# MIPI_DSI_TP.net
KiCad netlist of a schematic drawn in Altium Designer
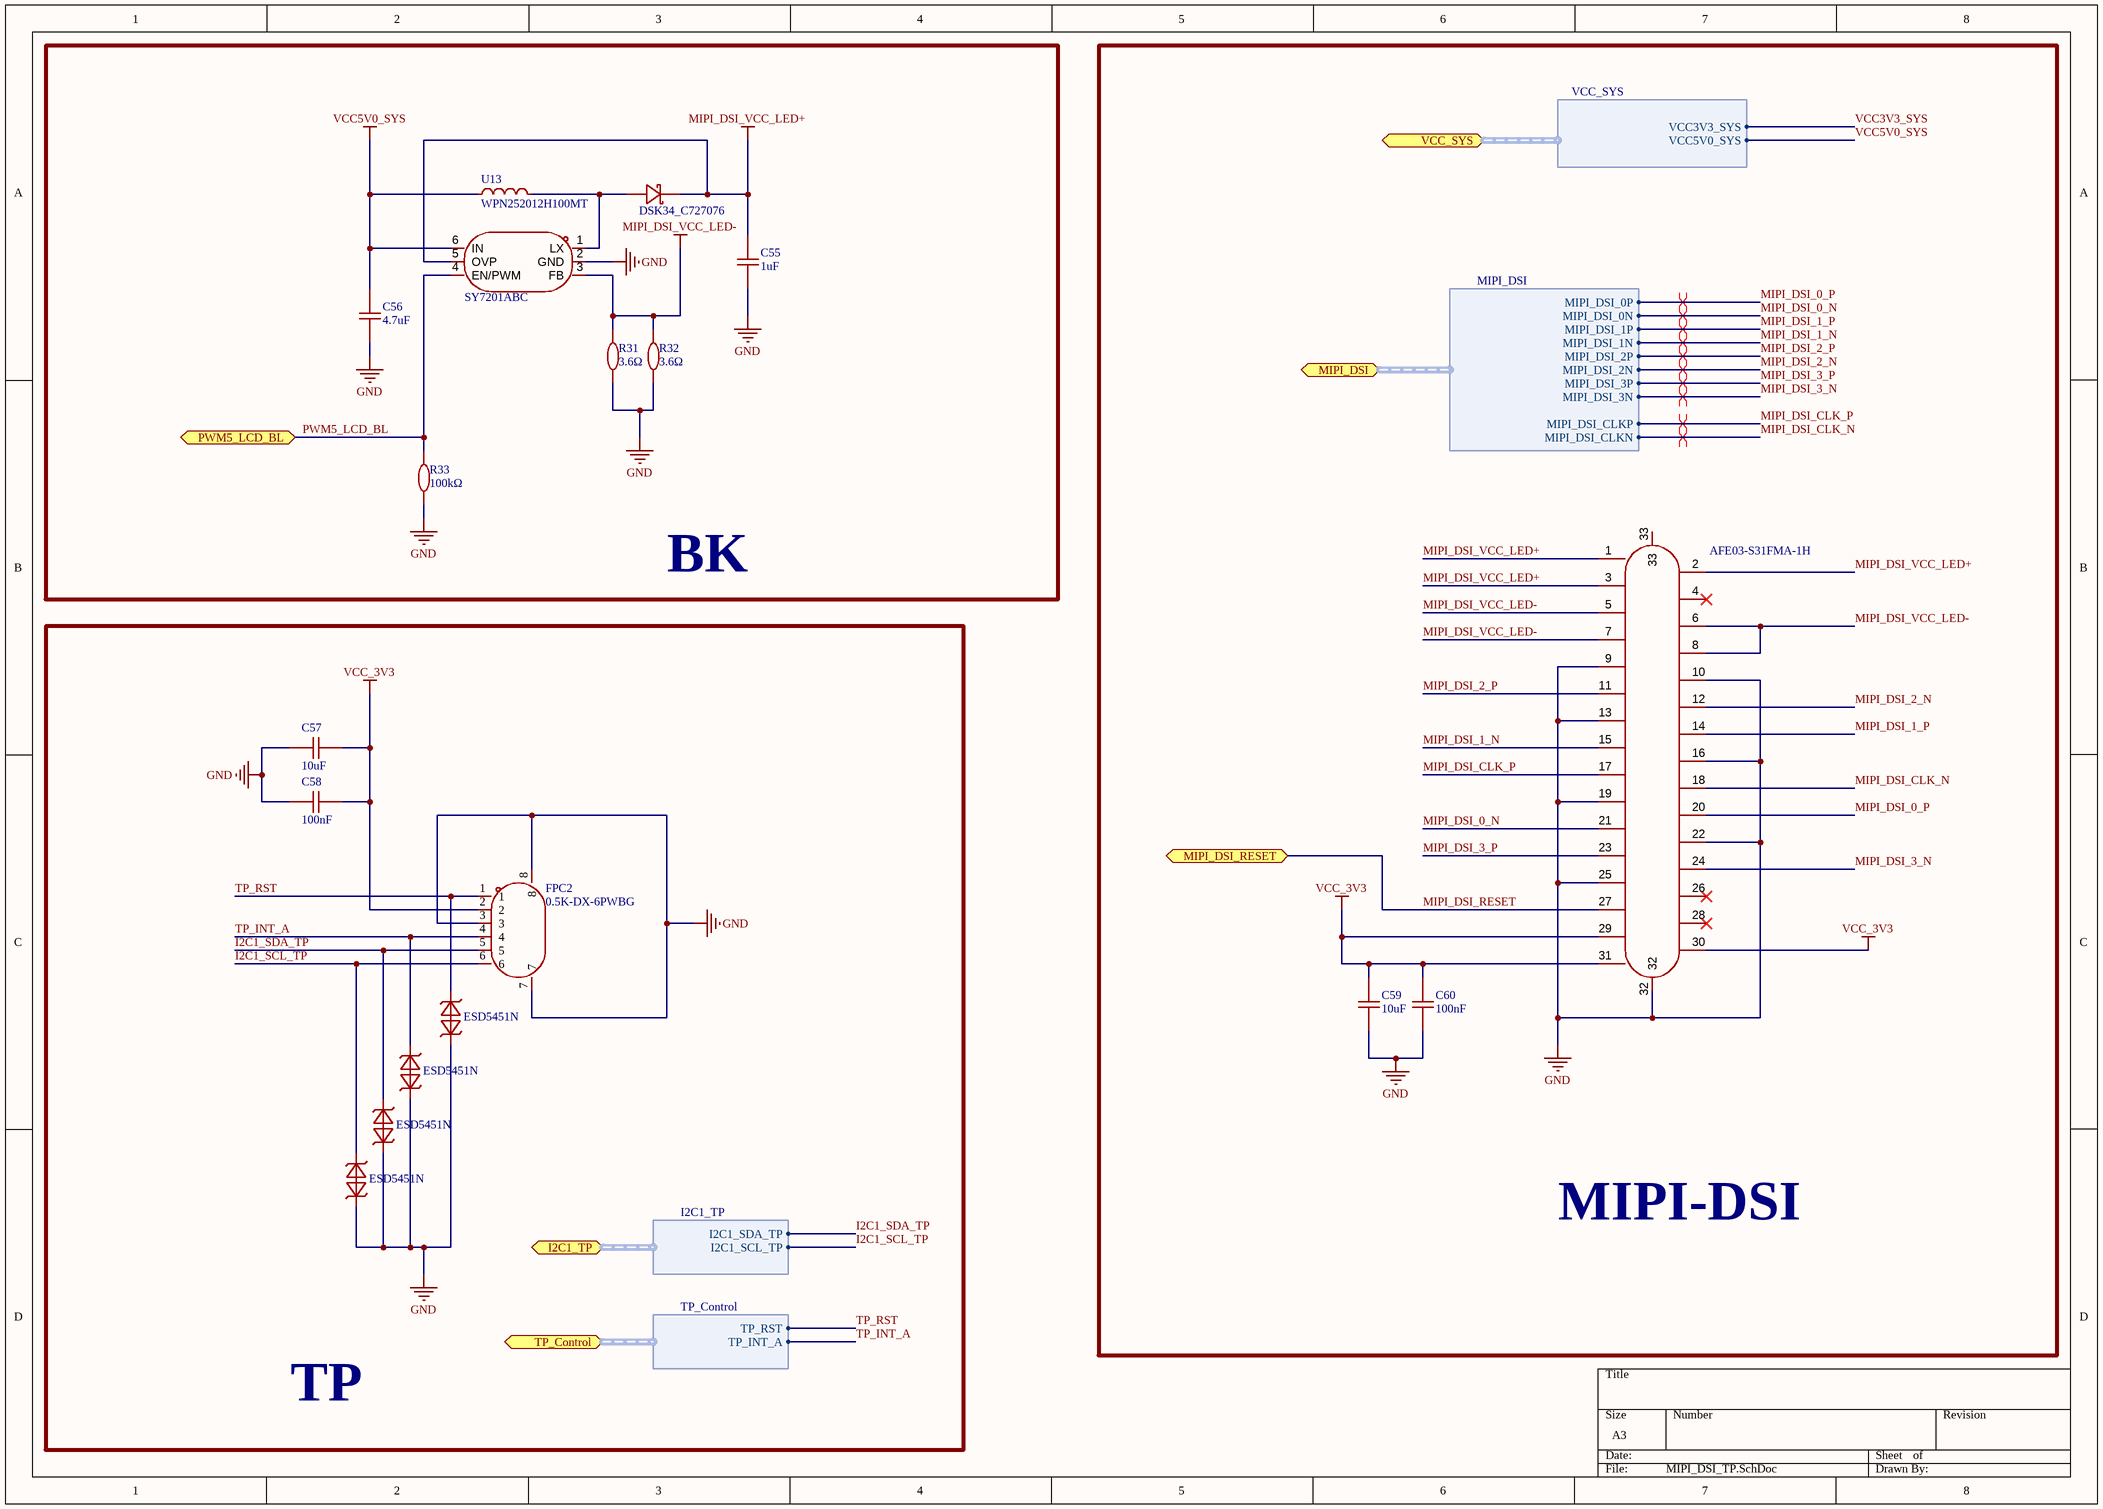
[diagram p0: MIPI_DSI_TP.SchDoc]

(export (version "E")
  (design (tool "Eeschema 10.0.6"))
  (components
    (comp (ref "C55")
      (value "1uF")
      (footprint "C0402")
      (description "50V 1uF X5R ±10% 0402 Ceramic Capacitors ROHS")
      (libsource (lib "RLC") (part "1uF"))
    )
    (comp (ref "C56")
      (value "4.7uF")
      (footprint "C0402")
      (description "10V 4.7uF X5R ±20% 0402 Ceramic Capacitors ROHS")
      (libsource (lib "RLC") (part "4.7uF"))
    )
    (comp (ref "C57")
      (value "10uF")
      (footprint "C0603")
      (description "10V 10uF X5R ±10% 0603 Ceramic Capacitors ROHS")
      (libsource (lib "RLC") (part "10uF"))
    )
    (comp (ref "C58")
      (value "100nF")
      (footprint "C0402")
      (description "50V 100nF X7R ±10% 0402 Ceramic Capacitors ROHS")
      (libsource (lib "RLC") (part "100nF"))
    )
    (comp (ref "C59")
      (value "10uF")
      (footprint "C0603")
      (description "10V 10uF X5R ±10% 0603 Ceramic Capacitors ROHS")
      (libsource (lib "RLC") (part "10uF"))
    )
    (comp (ref "C60")
      (value "100nF")
      (footprint "C0402")
      (description "50V 100nF X7R ±10% 0402 Ceramic Capacitors ROHS")
      (libsource (lib "RLC") (part "100nF"))
    )
    (comp (ref "D8")
      (value "DSK34_C727076")
      (footprint "SOD-323_L1.8-W1.3-LS2.5-RD")
      (libsource (lib "LED") (part "DSK34_C727076"))
    )
    (comp (ref "FPC1")
      (value "AFE03-S31FMA-1H")
      (footprint "FPC-SMD_P0.30-31P_FGS-XJ-H1.0")
      (description "FPC SMD,P=0.3mm,卧贴")
      (libsource (lib "Connector") (part "AFE03-S31FMA-1H"))
    )
    (comp (ref "FPC2")
      (value "0.5K-DX-6PWBG")
      (footprint "FPC-SMD_6P-P0.50_DEALON_0.5K-DX-6PWB")
      (libsource (lib "Connector") (part "0.5K-DX-6PWBG"))
    )
    (comp (ref "R31")
      (value "3.6Ω")
      (footprint "R0603")
      (description "0603 3.6Ω ±1% 100mW 厚膜电阻")
      (libsource (lib "RLC") (part "3.6Ω"))
    )
    (comp (ref "R32")
      (value "3.6Ω")
      (footprint "R0603")
      (description "0603 3.6Ω ±1% 100mW 厚膜电阻")
      (libsource (lib "RLC") (part "3.6Ω"))
    )
    (comp (ref "R33")
      (value "100kΩ")
      (footprint "R0402")
      (description "100kΩ 62.5mW 50V ±100ppm/℃ Thick Film Resistor ±1% 0402 Chip Resistor - Surface Mount ROHS")
      (libsource (lib "RLC") (part "100kΩ"))
    )
    (comp (ref "U13")
      (value "WPN252012H100MT")
      (footprint "IND-SMD_L2.5-W2.0_WPN252012H")
      (description "10uH")
      (libsource (lib "RLC") (part "WPN252012H100MT"))
    )
    (comp (ref "U14")
      (value "SY7201ABC")
      (footprint "SOT-23-6_L2.9-W1.6-P0.95-LS2.8-BR")
      (libsource (lib "IC") (part "SY7201ABC"))
    )
    (comp (ref "U15")
      (value "ESD5451N")
      (footprint "DFN1006-2L-BI")
      (description "是双向 TVS（瞬态电压抑制器），专门用于保护连接到低速数据线和控制线的敏感电子元件，使其免受 ESD（静电放电）、EFT（电快速瞬变）和浪涌引起的过应力影响。")
      (libsource (lib "LED") (part "ESD5451N"))
    )
    (comp (ref "U16")
      (value "ESD5451N")
      (footprint "DFN1006-2L-BI")
      (description "是双向 TVS（瞬态电压抑制器），专门用于保护连接到低速数据线和控制线的敏感电子元件，使其免受 ESD（静电放电）、EFT（电快速瞬变）和浪涌引起的过应力影响。")
      (libsource (lib "LED") (part "ESD5451N"))
    )
    (comp (ref "U17")
      (value "ESD5451N")
      (footprint "DFN1006-2L-BI")
      (description "是双向 TVS（瞬态电压抑制器），专门用于保护连接到低速数据线和控制线的敏感电子元件，使其免受 ESD（静电放电）、EFT（电快速瞬变）和浪涌引起的过应力影响。")
      (libsource (lib "LED") (part "ESD5451N"))
    )
    (comp (ref "U18")
      (value "ESD5451N")
      (footprint "DFN1006-2L-BI")
      (description "是双向 TVS（瞬态电压抑制器），专门用于保护连接到低速数据线和控制线的敏感电子元件，使其免受 ESD（静电放电）、EFT（电快速瞬变）和浪涌引起的过应力影响。")
      (libsource (lib "LED") (part "ESD5451N"))
    )
  )
  (nets
    (net (code "5") (name "/I2C1_SCL_TP") (class "Default")
      (node (ref "FPC2") (pin "6") (pinfunction "6_6") (pintype "passive"))
      (node (ref "U18") (pin "2") (pinfunction "2_2") (pintype "passive"))
    )
    (net (code "6") (name "/I2C1_SDA_TP") (class "Default")
      (node (ref "FPC2") (pin "5") (pinfunction "5_5") (pintype "passive"))
      (node (ref "U17") (pin "2") (pinfunction "2_2") (pintype "passive"))
    )
    (net (code "7") (name "/MIPI_DSI_0_N") (class "Default")
      (node (ref "FPC1") (pin "21") (pinfunction "21_21") (pintype "passive"))
    )
    (net (code "8") (name "/MIPI_DSI_0_P") (class "Default")
      (node (ref "FPC1") (pin "20") (pinfunction "20_20") (pintype "passive"))
    )
    (net (code "9") (name "/MIPI_DSI_1_N") (class "Default")
      (node (ref "FPC1") (pin "15") (pinfunction "15_15") (pintype "passive"))
    )
    (net (code "10") (name "/MIPI_DSI_1_P") (class "Default")
      (node (ref "FPC1") (pin "14") (pinfunction "14_14") (pintype "passive"))
    )
    (net (code "11") (name "/MIPI_DSI_2_N") (class "Default")
      (node (ref "FPC1") (pin "12") (pinfunction "12_12") (pintype "passive"))
    )
    (net (code "12") (name "/MIPI_DSI_2_P") (class "Default")
      (node (ref "FPC1") (pin "11") (pinfunction "11_11") (pintype "passive"))
    )
    (net (code "13") (name "/MIPI_DSI_3_N") (class "Default")
      (node (ref "FPC1") (pin "24") (pinfunction "24_24") (pintype "passive"))
    )
    (net (code "14") (name "/MIPI_DSI_3_P") (class "Default")
      (node (ref "FPC1") (pin "23") (pinfunction "23_23") (pintype "passive"))
    )
    (net (code "15") (name "/MIPI_DSI_CLK_N") (class "Default")
      (node (ref "FPC1") (pin "18") (pinfunction "18_18") (pintype "passive"))
    )
    (net (code "16") (name "/MIPI_DSI_CLK_P") (class "Default")
      (node (ref "FPC1") (pin "17") (pinfunction "17_17") (pintype "passive"))
    )
    (net (code "17") (name "/MIPI_DSI_RESET") (class "Default")
      (node (ref "FPC1") (pin "27") (pinfunction "27_27") (pintype "passive"))
    )
    (net (code "18") (name "/PWM5_LCD_BL") (class "Default")
      (node (ref "R33") (pin "2") (pinfunction "2_2") (pintype "passive"))
      (node (ref "U14") (pin "4") (pinfunction "EN/PWM_4") (pintype "passive"))
    )
    (net (code "19") (name "/TP_INT_A") (class "Default")
      (node (ref "FPC2") (pin "4") (pinfunction "4_4") (pintype "passive"))
      (node (ref "U16") (pin "2") (pinfunction "2_2") (pintype "passive"))
    )
    (net (code "20") (name "/TP_RST") (class "Default")
      (node (ref "FPC2") (pin "1") (pinfunction "1_1") (pintype "passive"))
      (node (ref "U15") (pin "2") (pinfunction "2_2") (pintype "passive"))
    )
    (net (code "26") (name "GND") (class "Default")
      (node (ref "C55") (pin "1") (pinfunction "1_1") (pintype "passive"))
      (node (ref "C56") (pin "1") (pinfunction "1_1") (pintype "passive"))
      (node (ref "C57") (pin "1") (pinfunction "1_1") (pintype "passive"))
      (node (ref "C58") (pin "1") (pinfunction "1_1") (pintype "passive"))
      (node (ref "C59") (pin "1") (pinfunction "1_1") (pintype "passive"))
      (node (ref "C60") (pin "1") (pinfunction "1_1") (pintype "passive"))
      (node (ref "FPC1") (pin "10") (pinfunction "10_10") (pintype "passive"))
      (node (ref "FPC1") (pin "13") (pinfunction "13_13") (pintype "passive"))
      (node (ref "FPC1") (pin "16") (pinfunction "16_16") (pintype "passive"))
      (node (ref "FPC1") (pin "19") (pinfunction "19_19") (pintype "passive"))
      (node (ref "FPC1") (pin "22") (pinfunction "22_22") (pintype "passive"))
      (node (ref "FPC1") (pin "25") (pinfunction "25_25") (pintype "passive"))
      (node (ref "FPC1") (pin "32") (pinfunction "32_32") (pintype "passive"))
      (node (ref "FPC1") (pin "9") (pinfunction "9_9") (pintype "passive"))
      (node (ref "FPC2") (pin "3") (pinfunction "3_3") (pintype "passive"))
      (node (ref "FPC2") (pin "7") (pinfunction "7_7") (pintype "passive"))
      (node (ref "FPC2") (pin "8") (pinfunction "8_8") (pintype "passive"))
      (node (ref "R31") (pin "1") (pinfunction "1_1") (pintype "passive"))
      (node (ref "R32") (pin "1") (pinfunction "1_1") (pintype "passive"))
      (node (ref "R33") (pin "1") (pinfunction "1_1") (pintype "passive"))
      (node (ref "U14") (pin "2") (pinfunction "GND_2") (pintype "passive"))
      (node (ref "U15") (pin "1") (pinfunction "1_1") (pintype "passive"))
      (node (ref "U16") (pin "1") (pinfunction "1_1") (pintype "passive"))
      (node (ref "U17") (pin "1") (pinfunction "1_1") (pintype "passive"))
      (node (ref "U18") (pin "1") (pinfunction "1_1") (pintype "passive"))
    )
    (net (code "27") (name "MIPI_DSI_VCC_LED+") (class "Default")
      (node (ref "C55") (pin "2") (pinfunction "2_2") (pintype "passive"))
      (node (ref "D8") (pin "1") (pinfunction "K_1") (pintype "passive"))
      (node (ref "FPC1") (pin "1") (pinfunction "1_1") (pintype "passive"))
      (node (ref "FPC1") (pin "2") (pinfunction "2_2") (pintype "passive"))
      (node (ref "FPC1") (pin "3") (pinfunction "3_3") (pintype "passive"))
      (node (ref "U14") (pin "5") (pinfunction "OVP_5") (pintype "passive"))
    )
    (net (code "28") (name "MIPI_DSI_VCC_LED-") (class "Default")
      (node (ref "FPC1") (pin "5") (pinfunction "5_5") (pintype "passive"))
      (node (ref "FPC1") (pin "6") (pinfunction "6_6") (pintype "passive"))
      (node (ref "FPC1") (pin "7") (pinfunction "7_7") (pintype "passive"))
      (node (ref "FPC1") (pin "8") (pinfunction "8_8") (pintype "passive"))
      (node (ref "R31") (pin "2") (pinfunction "2_2") (pintype "passive"))
      (node (ref "R32") (pin "2") (pinfunction "2_2") (pintype "passive"))
      (node (ref "U14") (pin "3") (pinfunction "FB_3") (pintype "passive"))
    )
    (net (code "29") (name "Net-(D8-A)") (class "Default")
      (node (ref "D8") (pin "2") (pinfunction "A_2") (pintype "passive"))
      (node (ref "U13") (pin "2") (pinfunction "2_2") (pintype "passive"))
      (node (ref "U14") (pin "1") (pinfunction "LX_1") (pintype "passive"))
    )
    (net (code "30") (name "VCC5V0_SYS") (class "Default")
      (node (ref "C56") (pin "2") (pinfunction "2_2") (pintype "passive"))
      (node (ref "U13") (pin "1") (pinfunction "1_1") (pintype "passive"))
      (node (ref "U14") (pin "6") (pinfunction "IN_6") (pintype "passive"))
    )
    (net (code "31") (name "VCC_3V3") (class "Default")
      (node (ref "C57") (pin "2") (pinfunction "2_2") (pintype "passive"))
      (node (ref "C58") (pin "2") (pinfunction "2_2") (pintype "passive"))
      (node (ref "C59") (pin "2") (pinfunction "2_2") (pintype "passive"))
      (node (ref "C60") (pin "2") (pinfunction "2_2") (pintype "passive"))
      (node (ref "FPC1") (pin "29") (pinfunction "29_29") (pintype "passive"))
      (node (ref "FPC1") (pin "30") (pinfunction "30_30") (pintype "passive"))
      (node (ref "FPC1") (pin "31") (pinfunction "31_31") (pintype "passive"))
      (node (ref "FPC2") (pin "2") (pinfunction "2_2") (pintype "passive"))
    )
    (net (code "32") (name "unconnected-(FPC1-Pad4)") (class "Default")
      (node (ref "FPC1") (pin "4") (pinfunction "4_4") (pintype "passive+no_connect"))
    )
    (net (code "33") (name "unconnected-(FPC1-Pad26)") (class "Default")
      (node (ref "FPC1") (pin "26") (pinfunction "26_26") (pintype "passive+no_connect"))
    )
    (net (code "34") (name "unconnected-(FPC1-Pad28)") (class "Default")
      (node (ref "FPC1") (pin "28") (pinfunction "28_28") (pintype "passive+no_connect"))
    )
    (net (code "35") (name "unconnected-(FPC1-Pad33)") (class "Default")
      (node (ref "FPC1") (pin "33") (pinfunction "33_33") (pintype "passive"))
    )
  )
)
